# M1125X.net
KiCad netlist of a schematic drawn in EAGLE
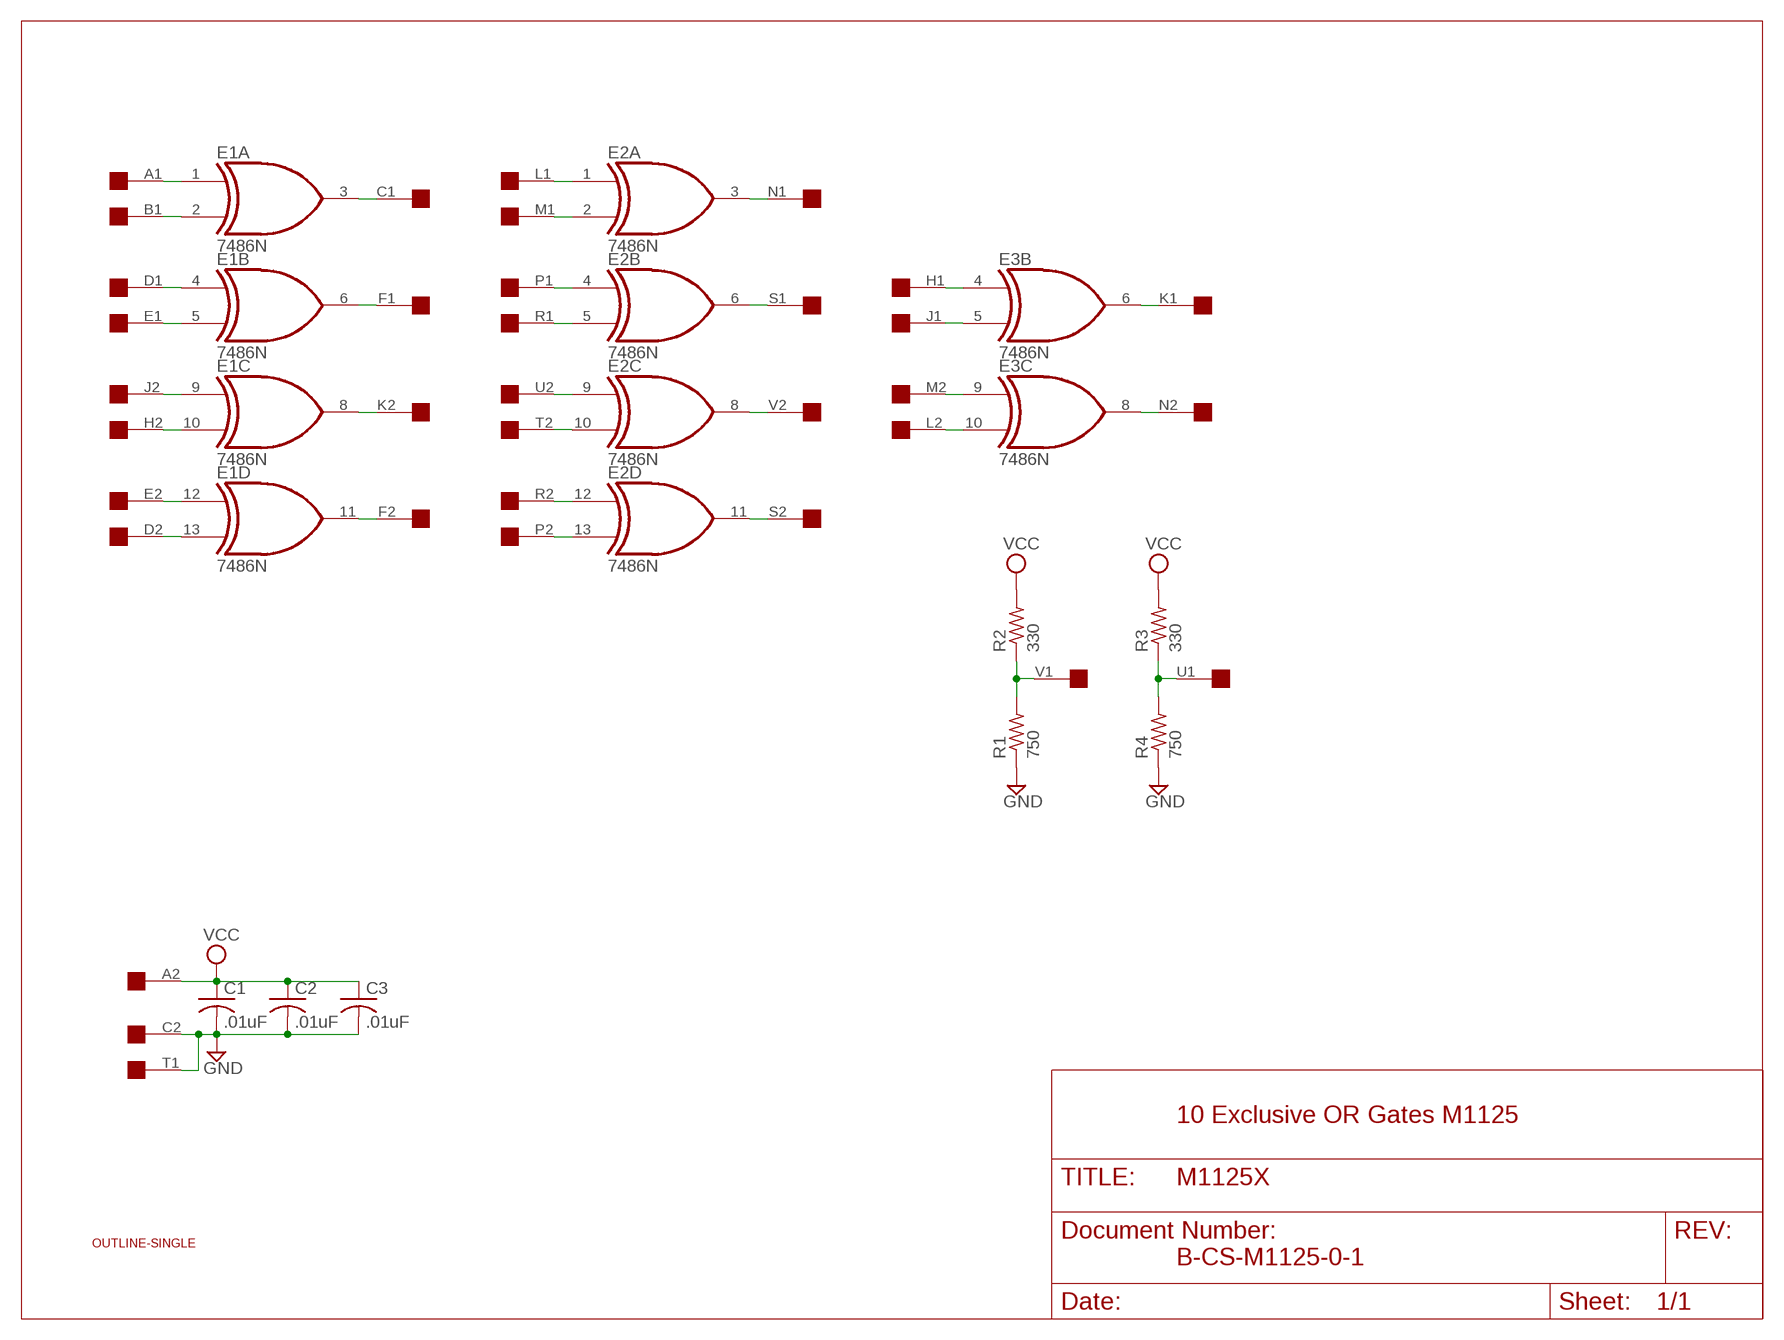
[diagram p0: schematic, sheet 1]

(export (version "E")
  (design (tool "Eeschema 10.0.6"))
  (components
    (comp (ref "C1")
      (value ".01uF")
      (footprint "eagle-import:C075-032X103")
      (libsource (lib "eagle-import") (part "C-US075-032X103"))
    )
    (comp (ref "C2")
      (value ".01uF")
      (footprint "eagle-import:C075-032X103")
      (libsource (lib "eagle-import") (part "C-US075-032X103"))
    )
    (comp (ref "C3")
      (value ".01uF")
      (footprint "eagle-import:C075-032X103")
      (libsource (lib "eagle-import") (part "C-US075-032X103"))
    )
    (comp (ref "E1")
      (value "7486N")
      (footprint "eagle-import:DIL14")
      (libsource (lib "eagle-import") (part "7486N"))
    )
    (comp (ref "E2")
      (value "7486N")
      (footprint "eagle-import:DIL14")
      (libsource (lib "eagle-import") (part "7486N"))
    )
    (comp (ref "E3")
      (value "7486N")
      (footprint "eagle-import:DIL14")
      (libsource (lib "eagle-import") (part "7486N"))
    )
    (comp (ref "R1")
      (value "750")
      (footprint "eagle-import:0207_10")
      (libsource (lib "eagle-import") (part "R-US_0207/10"))
    )
    (comp (ref "R2")
      (value "330")
      (footprint "eagle-import:0207_10")
      (libsource (lib "eagle-import") (part "R-US_0207/10"))
    )
    (comp (ref "R3")
      (value "330")
      (footprint "eagle-import:0207_10")
      (libsource (lib "eagle-import") (part "R-US_0207/10"))
    )
    (comp (ref "R4")
      (value "750")
      (footprint "eagle-import:0207_10")
      (libsource (lib "eagle-import") (part "R-US_0207/10"))
    )
    (comp (ref "U$1")
      (value "OUTLINE-SINGLE")
      (footprint "eagle-import:SINGLE")
      (libsource (lib "eagle-import") (part "OUTLINE-SINGLE"))
    )
    (comp (ref "U$2")
      (value "SINGLE")
      (footprint "eagle-import:EDGE-CON2")
      (libsource (lib "eagle-import") (part "SINGLE"))
    )
  )
  (nets
    (net (code "1") (name "GND") (class "Default")
      (node (ref "C1") (pin "2") (pinfunction "2_2") (pintype "passive"))
      (node (ref "C2") (pin "2") (pinfunction "2_2") (pintype "passive"))
      (node (ref "C3") (pin "2") (pinfunction "2_2") (pintype "passive"))
      (node (ref "R1") (pin "1") (pinfunction "1_1") (pintype "passive"))
      (node (ref "R4") (pin "1") (pinfunction "1_1") (pintype "passive"))
      (node (ref "U$2") (pin "C2") (pinfunction "1_C2") (pintype "bidirectional"))
      (node (ref "U$2") (pin "T1") (pinfunction "1_T1") (pintype "bidirectional"))
    )
    (net (code "2") (name "Net-(E1A-I0)") (class "Default")
      (node (ref "E1") (pin "1") (pinfunction "I0_1") (pintype "input"))
      (node (ref "U$2") (pin "A1") (pinfunction "1_A1") (pintype "bidirectional"))
    )
    (net (code "3") (name "Net-(E1A-I1)") (class "Default")
      (node (ref "E1") (pin "2") (pinfunction "I1_2") (pintype "input"))
      (node (ref "U$2") (pin "B1") (pinfunction "1_B1") (pintype "bidirectional"))
    )
    (net (code "4") (name "Net-(E1A-O)") (class "Default")
      (node (ref "E1") (pin "3") (pinfunction "O_3") (pintype "output"))
      (node (ref "U$2") (pin "C1") (pinfunction "1_C1") (pintype "bidirectional"))
    )
    (net (code "5") (name "Net-(E1B-I0)") (class "Default")
      (node (ref "E1") (pin "4") (pinfunction "I0_4") (pintype "input"))
      (node (ref "U$2") (pin "D1") (pinfunction "1_D1") (pintype "bidirectional"))
    )
    (net (code "6") (name "Net-(E1B-I1)") (class "Default")
      (node (ref "E1") (pin "5") (pinfunction "I1_5") (pintype "input"))
      (node (ref "U$2") (pin "E1") (pinfunction "1_E1") (pintype "bidirectional"))
    )
    (net (code "7") (name "Net-(E1B-O)") (class "Default")
      (node (ref "E1") (pin "6") (pinfunction "O_6") (pintype "output"))
      (node (ref "U$2") (pin "F1") (pinfunction "1_F1") (pintype "bidirectional"))
    )
    (net (code "8") (name "Net-(E1C-I0)") (class "Default")
      (node (ref "E1") (pin "9") (pinfunction "I0_9") (pintype "input"))
      (node (ref "U$2") (pin "J2") (pinfunction "1_J2") (pintype "bidirectional"))
    )
    (net (code "9") (name "Net-(E1C-I1)") (class "Default")
      (node (ref "E1") (pin "10") (pinfunction "I1_10") (pintype "input"))
      (node (ref "U$2") (pin "H2") (pinfunction "1_H2") (pintype "bidirectional"))
    )
    (net (code "10") (name "Net-(E1C-O)") (class "Default")
      (node (ref "E1") (pin "8") (pinfunction "O_8") (pintype "output"))
      (node (ref "U$2") (pin "K2") (pinfunction "1_K2") (pintype "bidirectional"))
    )
    (net (code "11") (name "Net-(E1D-I0)") (class "Default")
      (node (ref "E1") (pin "12") (pinfunction "I0_12") (pintype "input"))
      (node (ref "U$2") (pin "E2") (pinfunction "1_E2") (pintype "bidirectional"))
    )
    (net (code "12") (name "Net-(E1D-I1)") (class "Default")
      (node (ref "E1") (pin "13") (pinfunction "I1_13") (pintype "input"))
      (node (ref "U$2") (pin "D2") (pinfunction "1_D2") (pintype "bidirectional"))
    )
    (net (code "13") (name "Net-(E1D-O)") (class "Default")
      (node (ref "E1") (pin "11") (pinfunction "O_11") (pintype "output"))
      (node (ref "U$2") (pin "F2") (pinfunction "1_F2") (pintype "bidirectional"))
    )
    (net (code "14") (name "Net-(E2A-I0)") (class "Default")
      (node (ref "E2") (pin "1") (pinfunction "I0_1") (pintype "input"))
      (node (ref "U$2") (pin "L1") (pinfunction "1_L1") (pintype "bidirectional"))
    )
    (net (code "15") (name "Net-(E2A-I1)") (class "Default")
      (node (ref "E2") (pin "2") (pinfunction "I1_2") (pintype "input"))
      (node (ref "U$2") (pin "M1") (pinfunction "1_M1") (pintype "bidirectional"))
    )
    (net (code "16") (name "Net-(E2A-O)") (class "Default")
      (node (ref "E2") (pin "3") (pinfunction "O_3") (pintype "output"))
      (node (ref "U$2") (pin "N1") (pinfunction "1_N1") (pintype "bidirectional"))
    )
    (net (code "17") (name "Net-(E2B-I0)") (class "Default")
      (node (ref "E2") (pin "4") (pinfunction "I0_4") (pintype "input"))
      (node (ref "U$2") (pin "P1") (pinfunction "1_P1") (pintype "bidirectional"))
    )
    (net (code "18") (name "Net-(E2B-I1)") (class "Default")
      (node (ref "E2") (pin "5") (pinfunction "I1_5") (pintype "input"))
      (node (ref "U$2") (pin "R1") (pinfunction "1_R1") (pintype "bidirectional"))
    )
    (net (code "19") (name "Net-(E2B-O)") (class "Default")
      (node (ref "E2") (pin "6") (pinfunction "O_6") (pintype "output"))
      (node (ref "U$2") (pin "S1") (pinfunction "1_S1") (pintype "bidirectional"))
    )
    (net (code "20") (name "Net-(E2C-I0)") (class "Default")
      (node (ref "E2") (pin "9") (pinfunction "I0_9") (pintype "input"))
      (node (ref "U$2") (pin "U2") (pinfunction "1_U2") (pintype "bidirectional"))
    )
    (net (code "21") (name "Net-(E2C-I1)") (class "Default")
      (node (ref "E2") (pin "10") (pinfunction "I1_10") (pintype "input"))
      (node (ref "U$2") (pin "T2") (pinfunction "1_T2") (pintype "bidirectional"))
    )
    (net (code "22") (name "Net-(E2C-O)") (class "Default")
      (node (ref "E2") (pin "8") (pinfunction "O_8") (pintype "output"))
      (node (ref "U$2") (pin "V2") (pinfunction "1_V2") (pintype "bidirectional"))
    )
    (net (code "23") (name "Net-(E2D-I0)") (class "Default")
      (node (ref "E2") (pin "12") (pinfunction "I0_12") (pintype "input"))
      (node (ref "U$2") (pin "R2") (pinfunction "1_R2") (pintype "bidirectional"))
    )
    (net (code "24") (name "Net-(E2D-I1)") (class "Default")
      (node (ref "E2") (pin "13") (pinfunction "I1_13") (pintype "input"))
      (node (ref "U$2") (pin "P2") (pinfunction "1_P2") (pintype "bidirectional"))
    )
    (net (code "25") (name "Net-(E2D-O)") (class "Default")
      (node (ref "E2") (pin "11") (pinfunction "O_11") (pintype "output"))
      (node (ref "U$2") (pin "S2") (pinfunction "1_S2") (pintype "bidirectional"))
    )
    (net (code "26") (name "Net-(E3B-I0)") (class "Default")
      (node (ref "E3") (pin "4") (pinfunction "I0_4") (pintype "input"))
      (node (ref "U$2") (pin "H1") (pinfunction "1_H1") (pintype "bidirectional"))
    )
    (net (code "27") (name "Net-(E3B-I1)") (class "Default")
      (node (ref "E3") (pin "5") (pinfunction "I1_5") (pintype "input"))
      (node (ref "U$2") (pin "J1") (pinfunction "1_J1") (pintype "bidirectional"))
    )
    (net (code "28") (name "Net-(E3B-O)") (class "Default")
      (node (ref "E3") (pin "6") (pinfunction "O_6") (pintype "output"))
      (node (ref "U$2") (pin "K1") (pinfunction "1_K1") (pintype "bidirectional"))
    )
    (net (code "29") (name "Net-(E3C-I0)") (class "Default")
      (node (ref "E3") (pin "9") (pinfunction "I0_9") (pintype "input"))
      (node (ref "U$2") (pin "M2") (pinfunction "1_M2") (pintype "bidirectional"))
    )
    (net (code "30") (name "Net-(E3C-I1)") (class "Default")
      (node (ref "E3") (pin "10") (pinfunction "I1_10") (pintype "input"))
      (node (ref "U$2") (pin "L2") (pinfunction "1_L2") (pintype "bidirectional"))
    )
    (net (code "31") (name "Net-(E3C-O)") (class "Default")
      (node (ref "E3") (pin "8") (pinfunction "O_8") (pintype "output"))
      (node (ref "U$2") (pin "N2") (pinfunction "1_N2") (pintype "bidirectional"))
    )
    (net (code "32") (name "Net-(U$2AG-1)") (class "Default")
      (node (ref "R3") (pin "1") (pinfunction "1_1") (pintype "passive"))
      (node (ref "R4") (pin "2") (pinfunction "2_2") (pintype "passive"))
      (node (ref "U$2") (pin "U1") (pinfunction "1_U1") (pintype "bidirectional"))
    )
    (net (code "33") (name "Net-(U$2AI-1)") (class "Default")
      (node (ref "R1") (pin "2") (pinfunction "2_2") (pintype "passive"))
      (node (ref "R2") (pin "1") (pinfunction "1_1") (pintype "passive"))
      (node (ref "U$2") (pin "V1") (pinfunction "1_V1") (pintype "bidirectional"))
    )
    (net (code "34") (name "VCC") (class "Default")
      (node (ref "C1") (pin "1") (pinfunction "1_1") (pintype "passive"))
      (node (ref "C2") (pin "1") (pinfunction "1_1") (pintype "passive"))
      (node (ref "C3") (pin "1") (pinfunction "1_1") (pintype "passive"))
      (node (ref "R2") (pin "2") (pinfunction "2_2") (pintype "passive"))
      (node (ref "R3") (pin "2") (pinfunction "2_2") (pintype "passive"))
      (node (ref "U$2") (pin "A2") (pinfunction "1_A2") (pintype "bidirectional"))
    )
  )
)
